# Digital_ISO.net
KiCad netlist of a schematic drawn in Altium Designer
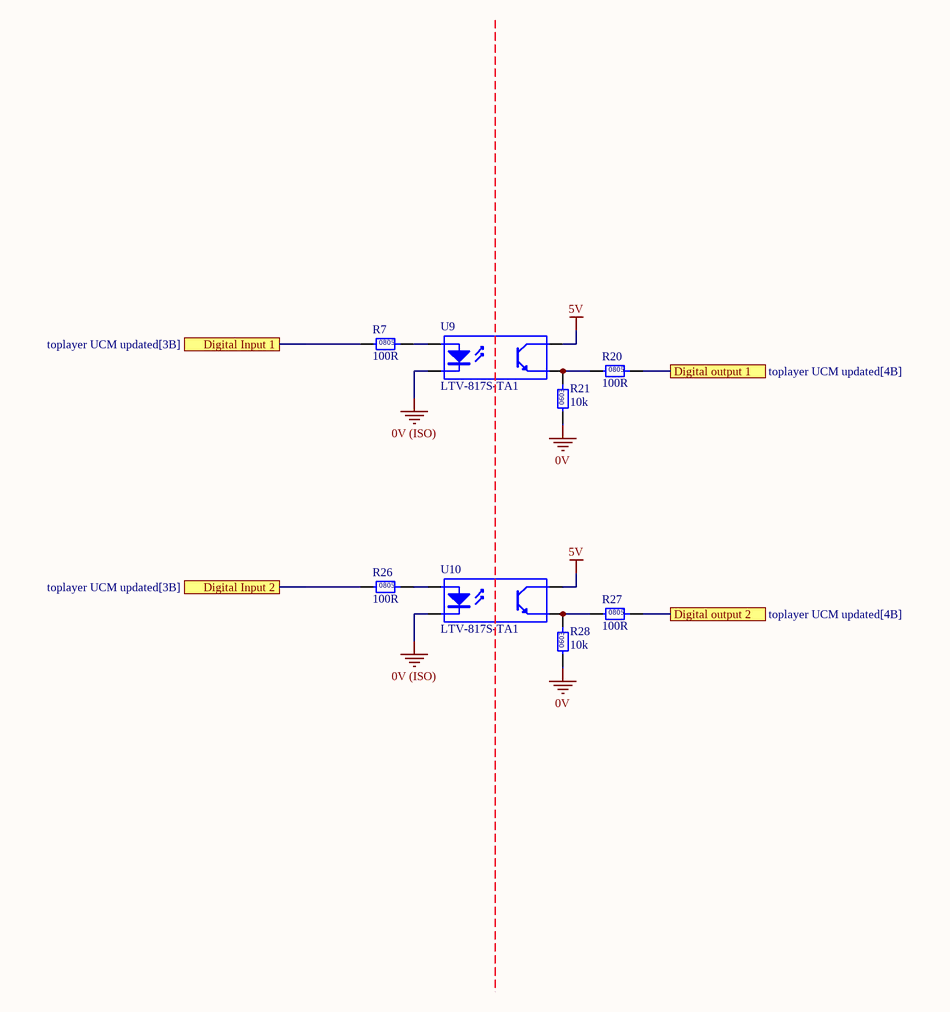
[diagram p0: Digital ISO.SchDoc]

(export (version "E")
  (design (tool "Eeschema 10.0.6"))
  (components
    (comp (ref "R7")
      (value "100R")
      (footprint "0805")
      (fields
        (field (name "PART NUMBER") "RC0805FR07100RL")
        (field (name "MANUFACTURER") "YAGEO")
        (field (name "TOLERANCE") "0.01")
      )
      (libsource (lib "ts_standard_library") (part "Resistor 0805"))
    )
    (comp (ref "R20")
      (value "100R")
      (footprint "0805")
      (fields
        (field (name "PART NUMBER") "RC0805FR07100RL")
        (field (name "MANUFACTURER") "YAGEO")
        (field (name "TOLERANCE") "0.01")
      )
      (libsource (lib "ts_standard_library") (part "Resistor 0805"))
    )
    (comp (ref "R21")
      (value "10k")
      (footprint "0603")
      (fields
        (field (name "PART NUMBER") "RC0603FR-0710KL")
        (field (name "MANUFACTURER") "YAGEO")
        (field (name "TOLERANCE") "0.01")
      )
      (libsource (lib "ts_standard_library") (part "Resistor 0603"))
    )
    (comp (ref "R26")
      (value "100R")
      (footprint "0805")
      (fields
        (field (name "PART NUMBER") "RC0805FR07100RL")
        (field (name "MANUFACTURER") "YAGEO")
        (field (name "TOLERANCE") "0.01")
      )
      (libsource (lib "ts_standard_library") (part "Resistor 0805"))
    )
    (comp (ref "R27")
      (value "100R")
      (footprint "0805")
      (fields
        (field (name "PART NUMBER") "RC0805FR07100RL")
        (field (name "MANUFACTURER") "YAGEO")
        (field (name "TOLERANCE") "0.01")
      )
      (libsource (lib "ts_standard_library") (part "Resistor 0805"))
    )
    (comp (ref "R28")
      (value "10k")
      (footprint "0603")
      (fields
        (field (name "PART NUMBER") "RC0603FR-0710KL")
        (field (name "MANUFACTURER") "YAGEO")
        (field (name "TOLERANCE") "0.01")
      )
      (libsource (lib "ts_standard_library") (part "Resistor 0603"))
    )
    (comp (ref "U9")
      (value "LTV-817S-TA1")
      (footprint "ON 4-SMD")
      (description "35V 50ma Optocoupler (VF=1.2V)")
      (fields
        (field (name "MANUFACTURER") "Lite-On Inc")
        (field (name "DIGIKEY PART NUMBER") "160-1893-2-ND")
      )
      (libsource (lib "ts_20-standard-library") (part "LTV-817S-TA1"))
    )
    (comp (ref "U10")
      (value "LTV-817S-TA1")
      (footprint "ON 4-SMD")
      (description "35V 50ma Optocoupler (VF=1.2V)")
      (fields
        (field (name "MANUFACTURER") "Lite-On Inc")
        (field (name "DIGIKEY PART NUMBER") "160-1893-2-ND")
      )
      (libsource (lib "ts_20-standard-library") (part "LTV-817S-TA1"))
    )
  )
  (nets
    (net (code "1") (name "/Digital Input 1") (class "Default")
      (node (ref "R7") (pin "1") (pinfunction "1_1") (pintype "passive"))
    )
    (net (code "2") (name "/Digital Input 2") (class "Default")
      (node (ref "R26") (pin "1") (pinfunction "1_1") (pintype "passive"))
    )
    (net (code "3") (name "/Digital output 1") (class "Default")
      (node (ref "R20") (pin "2") (pinfunction "2_2") (pintype "passive"))
    )
    (net (code "4") (name "/Digital output 2") (class "Default")
      (node (ref "R27") (pin "2") (pinfunction "2_2") (pintype "passive"))
    )
    (net (code "5") (name "0V") (class "Default")
      (node (ref "R21") (pin "1") (pinfunction "1_1") (pintype "passive"))
      (node (ref "R28") (pin "1") (pinfunction "1_1") (pintype "passive"))
    )
    (net (code "6") (name "0V (ISO)") (class "Default")
      (node (ref "U10") (pin "2") (pinfunction "K_2") (pintype "passive"))
      (node (ref "U9") (pin "2") (pinfunction "K_2") (pintype "passive"))
    )
    (net (code "7") (name "5V") (class "Default")
      (node (ref "U10") (pin "4") (pinfunction "C_4") (pintype "passive"))
      (node (ref "U9") (pin "4") (pinfunction "C_4") (pintype "passive"))
    )
    (net (code "8") (name "Net-(U9-A)") (class "Default")
      (node (ref "R7") (pin "2") (pinfunction "2_2") (pintype "passive"))
      (node (ref "U9") (pin "1") (pinfunction "A_1") (pintype "passive"))
    )
    (net (code "9") (name "Net-(U9-E)") (class "Default")
      (node (ref "R20") (pin "1") (pinfunction "1_1") (pintype "passive"))
      (node (ref "R21") (pin "2") (pinfunction "2_2") (pintype "passive"))
      (node (ref "U9") (pin "3") (pinfunction "E_3") (pintype "passive"))
    )
    (net (code "10") (name "Net-(U10-A)") (class "Default")
      (node (ref "R26") (pin "2") (pinfunction "2_2") (pintype "passive"))
      (node (ref "U10") (pin "1") (pinfunction "A_1") (pintype "passive"))
    )
    (net (code "11") (name "Net-(U10-E)") (class "Default")
      (node (ref "R27") (pin "1") (pinfunction "1_1") (pintype "passive"))
      (node (ref "R28") (pin "2") (pinfunction "2_2") (pintype "passive"))
      (node (ref "U10") (pin "3") (pinfunction "E_3") (pintype "passive"))
    )
  )
)
